# Stm-blth_connector.net
KiCad netlist of a schematic drawn in EAGLE
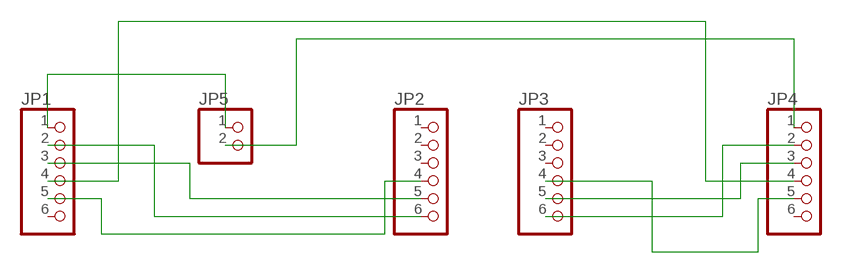
[diagram p0: schematic, sheet 1]

(export (version "E")
  (design (tool "Eeschema 10.0.6"))
  (components
    (comp (ref "JP1")
      (value "PINHD-1X6")
      (footprint "eagle-import:1X06")
      (libsource (lib "eagle-import") (part "PINHD-1X6"))
    )
    (comp (ref "JP2")
      (value "PINHD-1X6")
      (footprint "eagle-import:1X06")
      (libsource (lib "eagle-import") (part "PINHD-1X6"))
    )
    (comp (ref "JP3")
      (value "PINHD-1X6")
      (footprint "eagle-import:1X06")
      (libsource (lib "eagle-import") (part "PINHD-1X6"))
    )
    (comp (ref "JP4")
      (value "PINHD-1X6")
      (footprint "eagle-import:1X06")
      (libsource (lib "eagle-import") (part "PINHD-1X6"))
    )
    (comp (ref "JP5")
      (value "PINHD-1X2")
      (footprint "eagle-import:1X02")
      (libsource (lib "eagle-import") (part "PINHD-1X2"))
    )
  )
  (nets
    (net (code "1") (name "Net-(JP1-Pad1)") (class "Default")
      (node (ref "JP1") (pin "1") (pinfunction "1_1") (pintype "passive"))
      (node (ref "JP5") (pin "1") (pinfunction "1_1") (pintype "passive"))
    )
    (net (code "2") (name "Net-(JP1-Pad2)") (class "Default")
      (node (ref "JP1") (pin "2") (pinfunction "2_2") (pintype "passive"))
      (node (ref "JP2") (pin "6") (pinfunction "6_6") (pintype "passive"))
    )
    (net (code "3") (name "Net-(JP1-Pad3)") (class "Default")
      (node (ref "JP1") (pin "3") (pinfunction "3_3") (pintype "passive"))
      (node (ref "JP2") (pin "5") (pinfunction "5_5") (pintype "passive"))
    )
    (net (code "4") (name "Net-(JP1-Pad4)") (class "Default")
      (node (ref "JP1") (pin "4") (pinfunction "4_4") (pintype "passive"))
      (node (ref "JP4") (pin "4") (pinfunction "4_4") (pintype "passive"))
    )
    (net (code "5") (name "Net-(JP1-Pad5)") (class "Default")
      (node (ref "JP1") (pin "5") (pinfunction "5_5") (pintype "passive"))
      (node (ref "JP2") (pin "4") (pinfunction "4_4") (pintype "passive"))
    )
    (net (code "6") (name "Net-(JP3-Pad4)") (class "Default")
      (node (ref "JP3") (pin "4") (pinfunction "4_4") (pintype "passive"))
      (node (ref "JP4") (pin "5") (pinfunction "5_5") (pintype "passive"))
    )
    (net (code "7") (name "Net-(JP3-Pad5)") (class "Default")
      (node (ref "JP3") (pin "5") (pinfunction "5_5") (pintype "passive"))
      (node (ref "JP4") (pin "3") (pinfunction "3_3") (pintype "passive"))
    )
    (net (code "8") (name "Net-(JP3-Pad6)") (class "Default")
      (node (ref "JP3") (pin "6") (pinfunction "6_6") (pintype "passive"))
      (node (ref "JP4") (pin "2") (pinfunction "2_2") (pintype "passive"))
    )
    (net (code "9") (name "Net-(JP4-Pad1)") (class "Default")
      (node (ref "JP4") (pin "1") (pinfunction "1_1") (pintype "passive"))
      (node (ref "JP5") (pin "2") (pinfunction "2_2") (pintype "passive"))
    )
    (net (code "10") (name "unconnected-(JP1-Pad6)") (class "Default")
      (node (ref "JP1") (pin "6") (pinfunction "6_6") (pintype "passive"))
    )
    (net (code "11") (name "unconnected-(JP2-Pad1)") (class "Default")
      (node (ref "JP2") (pin "1") (pinfunction "1_1") (pintype "passive"))
    )
    (net (code "12") (name "unconnected-(JP2-Pad2)") (class "Default")
      (node (ref "JP2") (pin "2") (pinfunction "2_2") (pintype "passive"))
    )
    (net (code "13") (name "unconnected-(JP2-Pad3)") (class "Default")
      (node (ref "JP2") (pin "3") (pinfunction "3_3") (pintype "passive"))
    )
    (net (code "14") (name "unconnected-(JP3-Pad1)") (class "Default")
      (node (ref "JP3") (pin "1") (pinfunction "1_1") (pintype "passive"))
    )
    (net (code "15") (name "unconnected-(JP3-Pad2)") (class "Default")
      (node (ref "JP3") (pin "2") (pinfunction "2_2") (pintype "passive"))
    )
    (net (code "16") (name "unconnected-(JP3-Pad3)") (class "Default")
      (node (ref "JP3") (pin "3") (pinfunction "3_3") (pintype "passive"))
    )
    (net (code "17") (name "unconnected-(JP4-Pad6)") (class "Default")
      (node (ref "JP4") (pin "6") (pinfunction "6_6") (pintype "passive"))
    )
  )
)
